# kamstrup-wifi.net
KiCad netlist of a schematic drawn in EAGLE
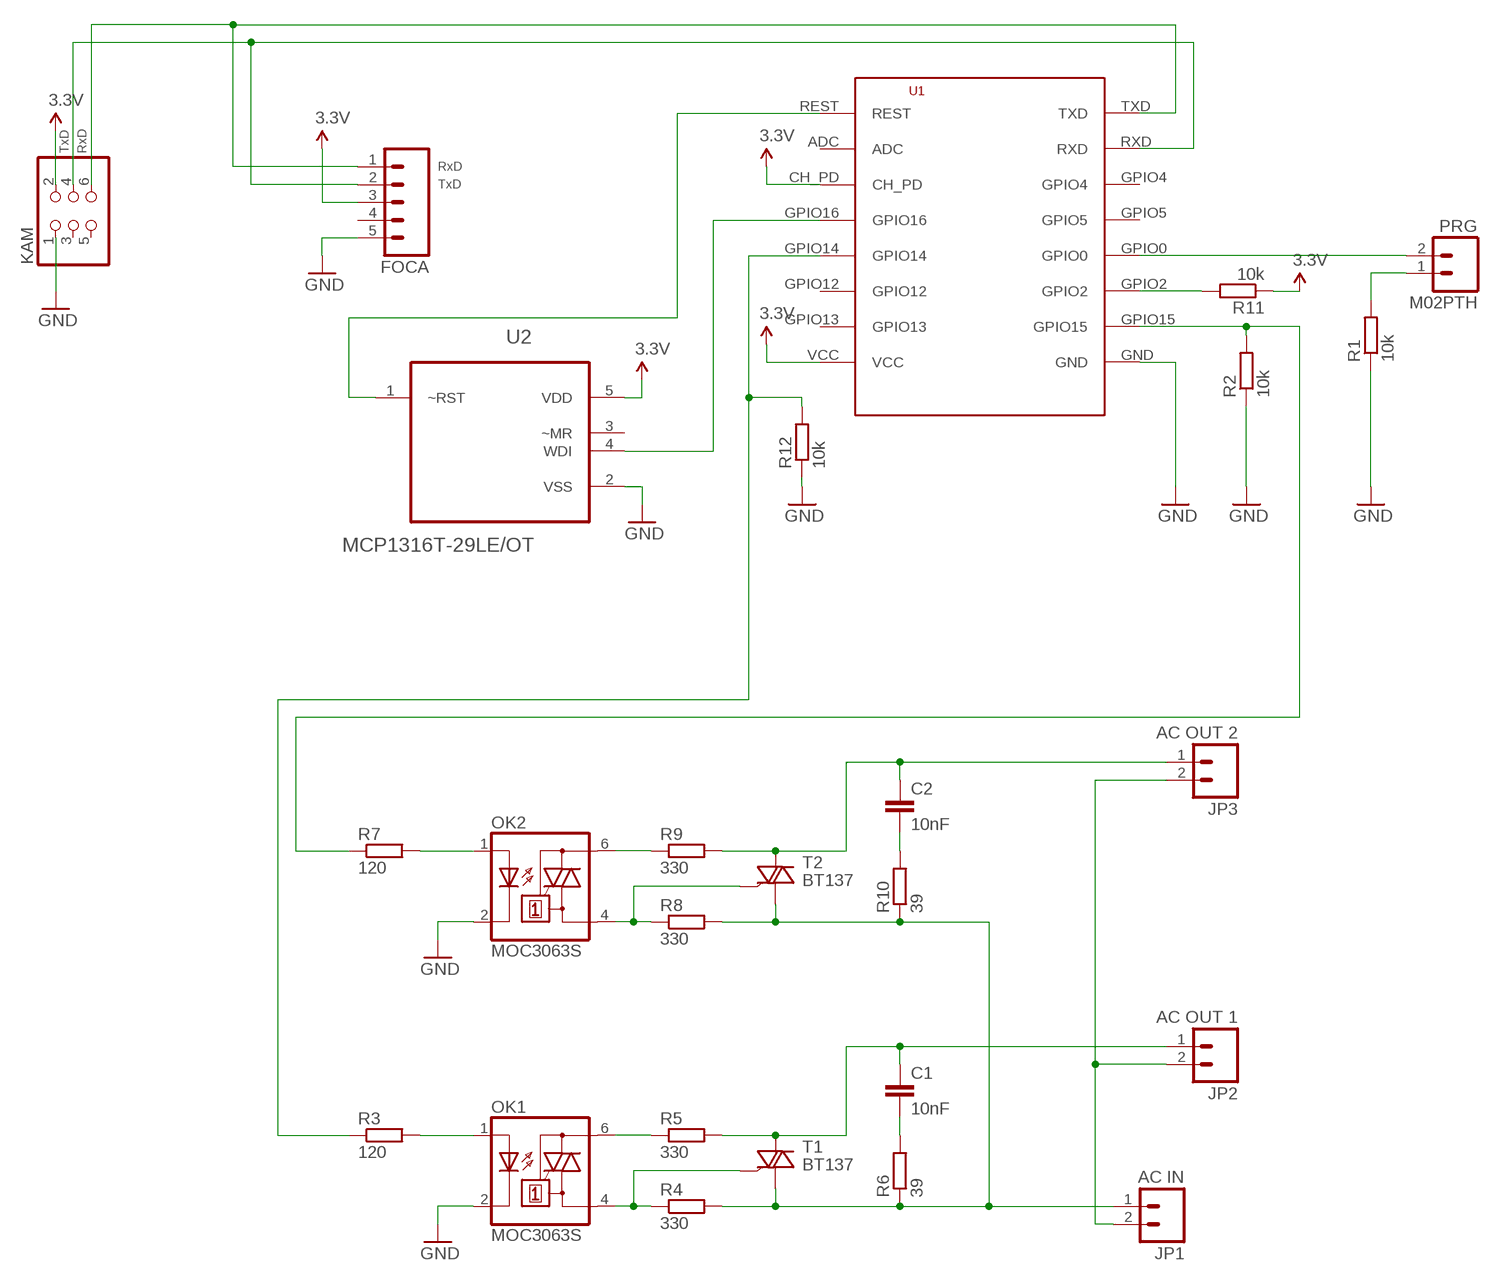
[diagram p0: schematic, sheet 1]

(export (version "E")
  (design (tool "Eeschema 10.0.6"))
  (components
    (comp (ref "C1")
      (value "10nF")
      (footprint "eagle-import:C1206")
      (libsource (lib "eagle-import") (part "C-EUC1206"))
    )
    (comp (ref "C2")
      (value "10nF")
      (footprint "eagle-import:C1206")
      (libsource (lib "eagle-import") (part "C-EUC1206"))
    )
    (comp (ref "FOCA")
      (value "M05PTH")
      (footprint "eagle-import:1X05")
      (libsource (lib "eagle-import") (part "M05PTH"))
    )
    (comp (ref "JP1")
      (value "AC IN")
      (footprint "eagle-import:SCREWTERMINAL-5MM-2")
      (libsource (lib "eagle-import") (part "TE Terminal Block 45 degrees_M025MM"))
    )
    (comp (ref "JP2")
      (value "AC OUT 1")
      (footprint "eagle-import:SCREWTERMINAL-5MM-2")
      (libsource (lib "eagle-import") (part "TE Terminal Block 45 degrees_M025MM"))
    )
    (comp (ref "JP3")
      (value "AC OUT 2")
      (footprint "eagle-import:SCREWTERMINAL-5MM-2")
      (libsource (lib "eagle-import") (part "TE Terminal Block 45 degrees_M025MM"))
    )
    (comp (ref "KAM")
      (value "PINHD-2X3")
      (footprint "eagle-import:2X03")
      (libsource (lib "eagle-import") (part "PINHD-2X3"))
    )
    (comp (ref "OK1")
      (value "MOC3063S")
      (footprint "eagle-import:DIL6-SMD")
      (fields (field (name "MF") "FAIRCHILD SEMICONDUCTOR") (field (name "MPN") "MOC3043SM"))
      (libsource (lib "eagle-import") (part "MOC30S43"))
    )
    (comp (ref "OK2")
      (value "MOC3063S")
      (footprint "eagle-import:DIL6-SMD")
      (fields (field (name "MF") "FAIRCHILD SEMICONDUCTOR") (field (name "MPN") "MOC3043SM"))
      (libsource (lib "eagle-import") (part "MOC30S43"))
    )
    (comp (ref "PRG")
      (value "M02PTH")
      (footprint "eagle-import:1X02")
      (libsource (lib "eagle-import") (part "M02PTH"))
    )
    (comp (ref "R1")
      (value "10k")
      (footprint "eagle-import:R0805")
      (libsource (lib "eagle-import") (part "R-EU_R0805"))
    )
    (comp (ref "R2")
      (value "10k")
      (footprint "eagle-import:R0805")
      (libsource (lib "eagle-import") (part "R-EU_R0805"))
    )
    (comp (ref "R3")
      (value "120")
      (footprint "eagle-import:R0805")
      (libsource (lib "eagle-import") (part "R-EU_R0805"))
    )
    (comp (ref "R4")
      (value "330")
      (footprint "eagle-import:R0805")
      (libsource (lib "eagle-import") (part "R-EU_R0805"))
    )
    (comp (ref "R5")
      (value "330")
      (footprint "eagle-import:R0805")
      (libsource (lib "eagle-import") (part "R-EU_R0805"))
    )
    (comp (ref "R6")
      (value "39")
      (footprint "eagle-import:R0805")
      (libsource (lib "eagle-import") (part "R-EU_R0805"))
    )
    (comp (ref "R7")
      (value "120")
      (footprint "eagle-import:R0805")
      (libsource (lib "eagle-import") (part "R-EU_R0805"))
    )
    (comp (ref "R8")
      (value "330")
      (footprint "eagle-import:R0805")
      (libsource (lib "eagle-import") (part "R-EU_R0805"))
    )
    (comp (ref "R9")
      (value "330")
      (footprint "eagle-import:R0805")
      (libsource (lib "eagle-import") (part "R-EU_R0805"))
    )
    (comp (ref "R10")
      (value "39")
      (footprint "eagle-import:R0805")
      (libsource (lib "eagle-import") (part "R-EU_R0805"))
    )
    (comp (ref "R11")
      (value "10k")
      (footprint "eagle-import:R0805")
      (libsource (lib "eagle-import") (part "R-EU_R0805"))
    )
    (comp (ref "R12")
      (value "10k")
      (footprint "eagle-import:R0805")
      (libsource (lib "eagle-import") (part "R-EU_R0805"))
    )
    (comp (ref "T1")
      (value "BT137")
      (footprint "eagle-import:SOT428")
      (libsource (lib "eagle-import") (part "BT137"))
    )
    (comp (ref "T2")
      (value "BT137")
      (footprint "eagle-import:SOT428")
      (libsource (lib "eagle-import") (part "BT137"))
    )
    (comp (ref "U1")
      (value "ESP8266-07")
      (footprint "eagle-import:ESP-07")
      (libsource (lib "eagle-import") (part "ESP8266-07"))
    )
    (comp (ref "U2")
      (value "MCP1316T-29LE/OT")
      (footprint "eagle-import:SOT95P270X145-5N")
      (libsource (lib "eagle-import") (part "MCP1316T-29LE/OT"))
    )
  )
  (nets
    (net (code "1") (name "3.3V") (class "Default")
      (node (ref "FOCA") (pin "3") (pinfunction "3_3") (pintype "passive"))
      (node (ref "KAM") (pin "2") (pinfunction "2_2") (pintype "passive"))
      (node (ref "R11") (pin "1") (pinfunction "1_1") (pintype "passive"))
      (node (ref "U1") (pin "CH_PD") (pinfunction "CH_PD_CH_PD") (pintype "bidirectional"))
      (node (ref "U1") (pin "VCC") (pinfunction "VCC_VCC") (pintype "bidirectional"))
      (node (ref "U2") (pin "5") (pinfunction "VDD_5") (pintype "power_in"))
    )
    (net (code "2") (name "GND") (class "Default")
      (node (ref "FOCA") (pin "5") (pinfunction "5_5") (pintype "passive"))
      (node (ref "KAM") (pin "1") (pinfunction "1_1") (pintype "passive"))
      (node (ref "OK1") (pin "2") (pinfunction "C_2") (pintype "passive"))
      (node (ref "OK2") (pin "2") (pinfunction "C_2") (pintype "passive"))
      (node (ref "R1") (pin "1") (pinfunction "1_1") (pintype "passive"))
      (node (ref "R12") (pin "1") (pinfunction "1_1") (pintype "passive"))
      (node (ref "R2") (pin "1") (pinfunction "1_1") (pintype "passive"))
      (node (ref "U1") (pin "GND") (pinfunction "GND_GND") (pintype "power_in"))
      (node (ref "U2") (pin "2") (pinfunction "VSS_2") (pintype "power_in"))
    )
    (net (code "3") (name "Net-(C1-Pad2)") (class "Default")
      (node (ref "C1") (pin "2") (pinfunction "2_2") (pintype "passive"))
      (node (ref "R6") (pin "2") (pinfunction "2_2") (pintype "passive"))
    )
    (net (code "4") (name "Net-(C2-Pad2)") (class "Default")
      (node (ref "C2") (pin "2") (pinfunction "2_2") (pintype "passive"))
      (node (ref "R10") (pin "2") (pinfunction "2_2") (pintype "passive"))
    )
    (net (code "5") (name "Net-(FOCA-Pad1)") (class "Default")
      (node (ref "FOCA") (pin "1") (pinfunction "1_1") (pintype "passive"))
      (node (ref "KAM") (pin "6") (pinfunction "6_6") (pintype "passive"))
      (node (ref "U1") (pin "TXD") (pinfunction "TXD_TXD") (pintype "bidirectional"))
    )
    (net (code "6") (name "Net-(FOCA-Pad2)") (class "Default")
      (node (ref "FOCA") (pin "2") (pinfunction "2_2") (pintype "passive"))
      (node (ref "KAM") (pin "4") (pinfunction "4_4") (pintype "passive"))
      (node (ref "U1") (pin "RXD") (pinfunction "RXD_RXD") (pintype "bidirectional"))
    )
    (net (code "7") (name "Net-(JP1-Pad2)") (class "Default")
      (node (ref "JP1") (pin "2") (pinfunction "2_2") (pintype "passive"))
      (node (ref "JP2") (pin "2") (pinfunction "2_2") (pintype "passive"))
      (node (ref "JP3") (pin "2") (pinfunction "2_2") (pintype "passive"))
    )
    (net (code "8") (name "Net-(OK1-A)") (class "Default")
      (node (ref "OK1") (pin "1") (pinfunction "A_1") (pintype "passive"))
      (node (ref "R3") (pin "2") (pinfunction "2_2") (pintype "passive"))
    )
    (net (code "9") (name "Net-(OK1-A1)") (class "Default")
      (node (ref "OK1") (pin "4") (pinfunction "A1_4") (pintype "passive"))
      (node (ref "R4") (pin "1") (pinfunction "1_1") (pintype "passive"))
      (node (ref "T1") (pin "3") (pinfunction "G_3") (pintype "passive"))
    )
    (net (code "10") (name "Net-(OK1-A2)") (class "Default")
      (node (ref "OK1") (pin "6") (pinfunction "A2_6") (pintype "passive"))
      (node (ref "R5") (pin "1") (pinfunction "1_1") (pintype "passive"))
    )
    (net (code "11") (name "Net-(OK2-A)") (class "Default")
      (node (ref "OK2") (pin "1") (pinfunction "A_1") (pintype "passive"))
      (node (ref "R7") (pin "2") (pinfunction "2_2") (pintype "passive"))
    )
    (net (code "12") (name "Net-(OK2-A1)") (class "Default")
      (node (ref "OK2") (pin "4") (pinfunction "A1_4") (pintype "passive"))
      (node (ref "R8") (pin "1") (pinfunction "1_1") (pintype "passive"))
      (node (ref "T2") (pin "3") (pinfunction "G_3") (pintype "passive"))
    )
    (net (code "13") (name "Net-(OK2-A2)") (class "Default")
      (node (ref "OK2") (pin "6") (pinfunction "A2_6") (pintype "passive"))
      (node (ref "R9") (pin "1") (pinfunction "1_1") (pintype "passive"))
    )
    (net (code "14") (name "Net-(PRG-Pad1)") (class "Default")
      (node (ref "PRG") (pin "1") (pinfunction "1_1") (pintype "passive"))
      (node (ref "R1") (pin "2") (pinfunction "2_2") (pintype "passive"))
    )
    (net (code "15") (name "Net-(PRG-Pad2)") (class "Default")
      (node (ref "PRG") (pin "2") (pinfunction "2_2") (pintype "passive"))
      (node (ref "U1") (pin "GPIO0") (pinfunction "GPIO0_GPIO0") (pintype "bidirectional"))
    )
    (net (code "16") (name "Net-(R2-Pad2)") (class "Default")
      (node (ref "R2") (pin "2") (pinfunction "2_2") (pintype "passive"))
      (node (ref "R7") (pin "1") (pinfunction "1_1") (pintype "passive"))
      (node (ref "U1") (pin "GPIO15") (pinfunction "GPIO15_GPIO15") (pintype "bidirectional"))
    )
    (net (code "17") (name "Net-(R11-Pad2)") (class "Default")
      (node (ref "R11") (pin "2") (pinfunction "2_2") (pintype "passive"))
      (node (ref "U1") (pin "GPIO2") (pinfunction "GPIO2_GPIO2") (pintype "bidirectional"))
    )
    (net (code "18") (name "Net-(R12-Pad2)") (class "Default")
      (node (ref "R12") (pin "2") (pinfunction "2_2") (pintype "passive"))
      (node (ref "R3") (pin "1") (pinfunction "1_1") (pintype "passive"))
      (node (ref "U1") (pin "GPIO14") (pinfunction "GPIO14_GPIO14") (pintype "bidirectional"))
    )
    (net (code "19") (name "Net-(T1-A1)") (class "Default")
      (node (ref "JP1") (pin "1") (pinfunction "1_1") (pintype "passive"))
      (node (ref "R10") (pin "1") (pinfunction "1_1") (pintype "passive"))
      (node (ref "R4") (pin "2") (pinfunction "2_2") (pintype "passive"))
      (node (ref "R6") (pin "1") (pinfunction "1_1") (pintype "passive"))
      (node (ref "R8") (pin "2") (pinfunction "2_2") (pintype "passive"))
      (node (ref "T1") (pin "1") (pinfunction "A1_1") (pintype "passive"))
      (node (ref "T2") (pin "1") (pinfunction "A1_1") (pintype "passive"))
    )
    (net (code "20") (name "Net-(T1-A2)") (class "Default")
      (node (ref "C1") (pin "1") (pinfunction "1_1") (pintype "passive"))
      (node (ref "JP2") (pin "1") (pinfunction "1_1") (pintype "passive"))
      (node (ref "R5") (pin "2") (pinfunction "2_2") (pintype "passive"))
      (node (ref "T1") (pin "4") (pinfunction "A2_4") (pintype "passive"))
    )
    (net (code "21") (name "Net-(T2-A2)") (class "Default")
      (node (ref "C2") (pin "1") (pinfunction "1_1") (pintype "passive"))
      (node (ref "JP3") (pin "1") (pinfunction "1_1") (pintype "passive"))
      (node (ref "R9") (pin "2") (pinfunction "2_2") (pintype "passive"))
      (node (ref "T2") (pin "4") (pinfunction "A2_4") (pintype "passive"))
    )
    (net (code "22") (name "Net-(U2-WDI)") (class "Default")
      (node (ref "U1") (pin "GPIO16") (pinfunction "GPIO16_GPIO16") (pintype "bidirectional"))
      (node (ref "U2") (pin "4") (pinfunction "WDI_4") (pintype "input"))
    )
    (net (code "23") (name "Net-(U2-~{RST})") (class "Default")
      (node (ref "U1") (pin "REST") (pinfunction "REST_REST") (pintype "bidirectional"))
      (node (ref "U2") (pin "1") (pinfunction "~{RST}_1") (pintype "output"))
    )
    (net (code "24") (name "unconnected-(FOCA-Pad4)") (class "Default")
      (node (ref "FOCA") (pin "4") (pinfunction "4_4") (pintype "passive"))
    )
    (net (code "25") (name "unconnected-(KAM-Pad3)") (class "Default")
      (node (ref "KAM") (pin "3") (pinfunction "3_3") (pintype "passive"))
    )
    (net (code "26") (name "unconnected-(KAM-Pad5)") (class "Default")
      (node (ref "KAM") (pin "5") (pinfunction "5_5") (pintype "passive"))
    )
    (net (code "27") (name "unconnected-(U1-PadADC)") (class "Default")
      (node (ref "U1") (pin "ADC") (pinfunction "ADC_ADC") (pintype "bidirectional"))
    )
    (net (code "28") (name "unconnected-(U1-PadGPIO4)") (class "Default")
      (node (ref "U1") (pin "GPIO4") (pinfunction "GPIO4_GPIO4") (pintype "bidirectional"))
    )
    (net (code "29") (name "unconnected-(U1-PadGPIO5)") (class "Default")
      (node (ref "U1") (pin "GPIO5") (pinfunction "GPIO5_GPIO5") (pintype "bidirectional"))
    )
    (net (code "30") (name "unconnected-(U1-PadGPIO12)") (class "Default")
      (node (ref "U1") (pin "GPIO12") (pinfunction "GPIO12_GPIO12") (pintype "bidirectional"))
    )
    (net (code "31") (name "unconnected-(U1-PadGPIO13)") (class "Default")
      (node (ref "U1") (pin "GPIO13") (pinfunction "GPIO13_GPIO13") (pintype "bidirectional"))
    )
    (net (code "32") (name "unconnected-(U2-~{MR}-Pad3)") (class "Default")
      (node (ref "U2") (pin "3") (pinfunction "~{MR}_3") (pintype "input"))
    )
  )
)
